# Comm.net
KiCad netlist of a schematic drawn in Altium Designer
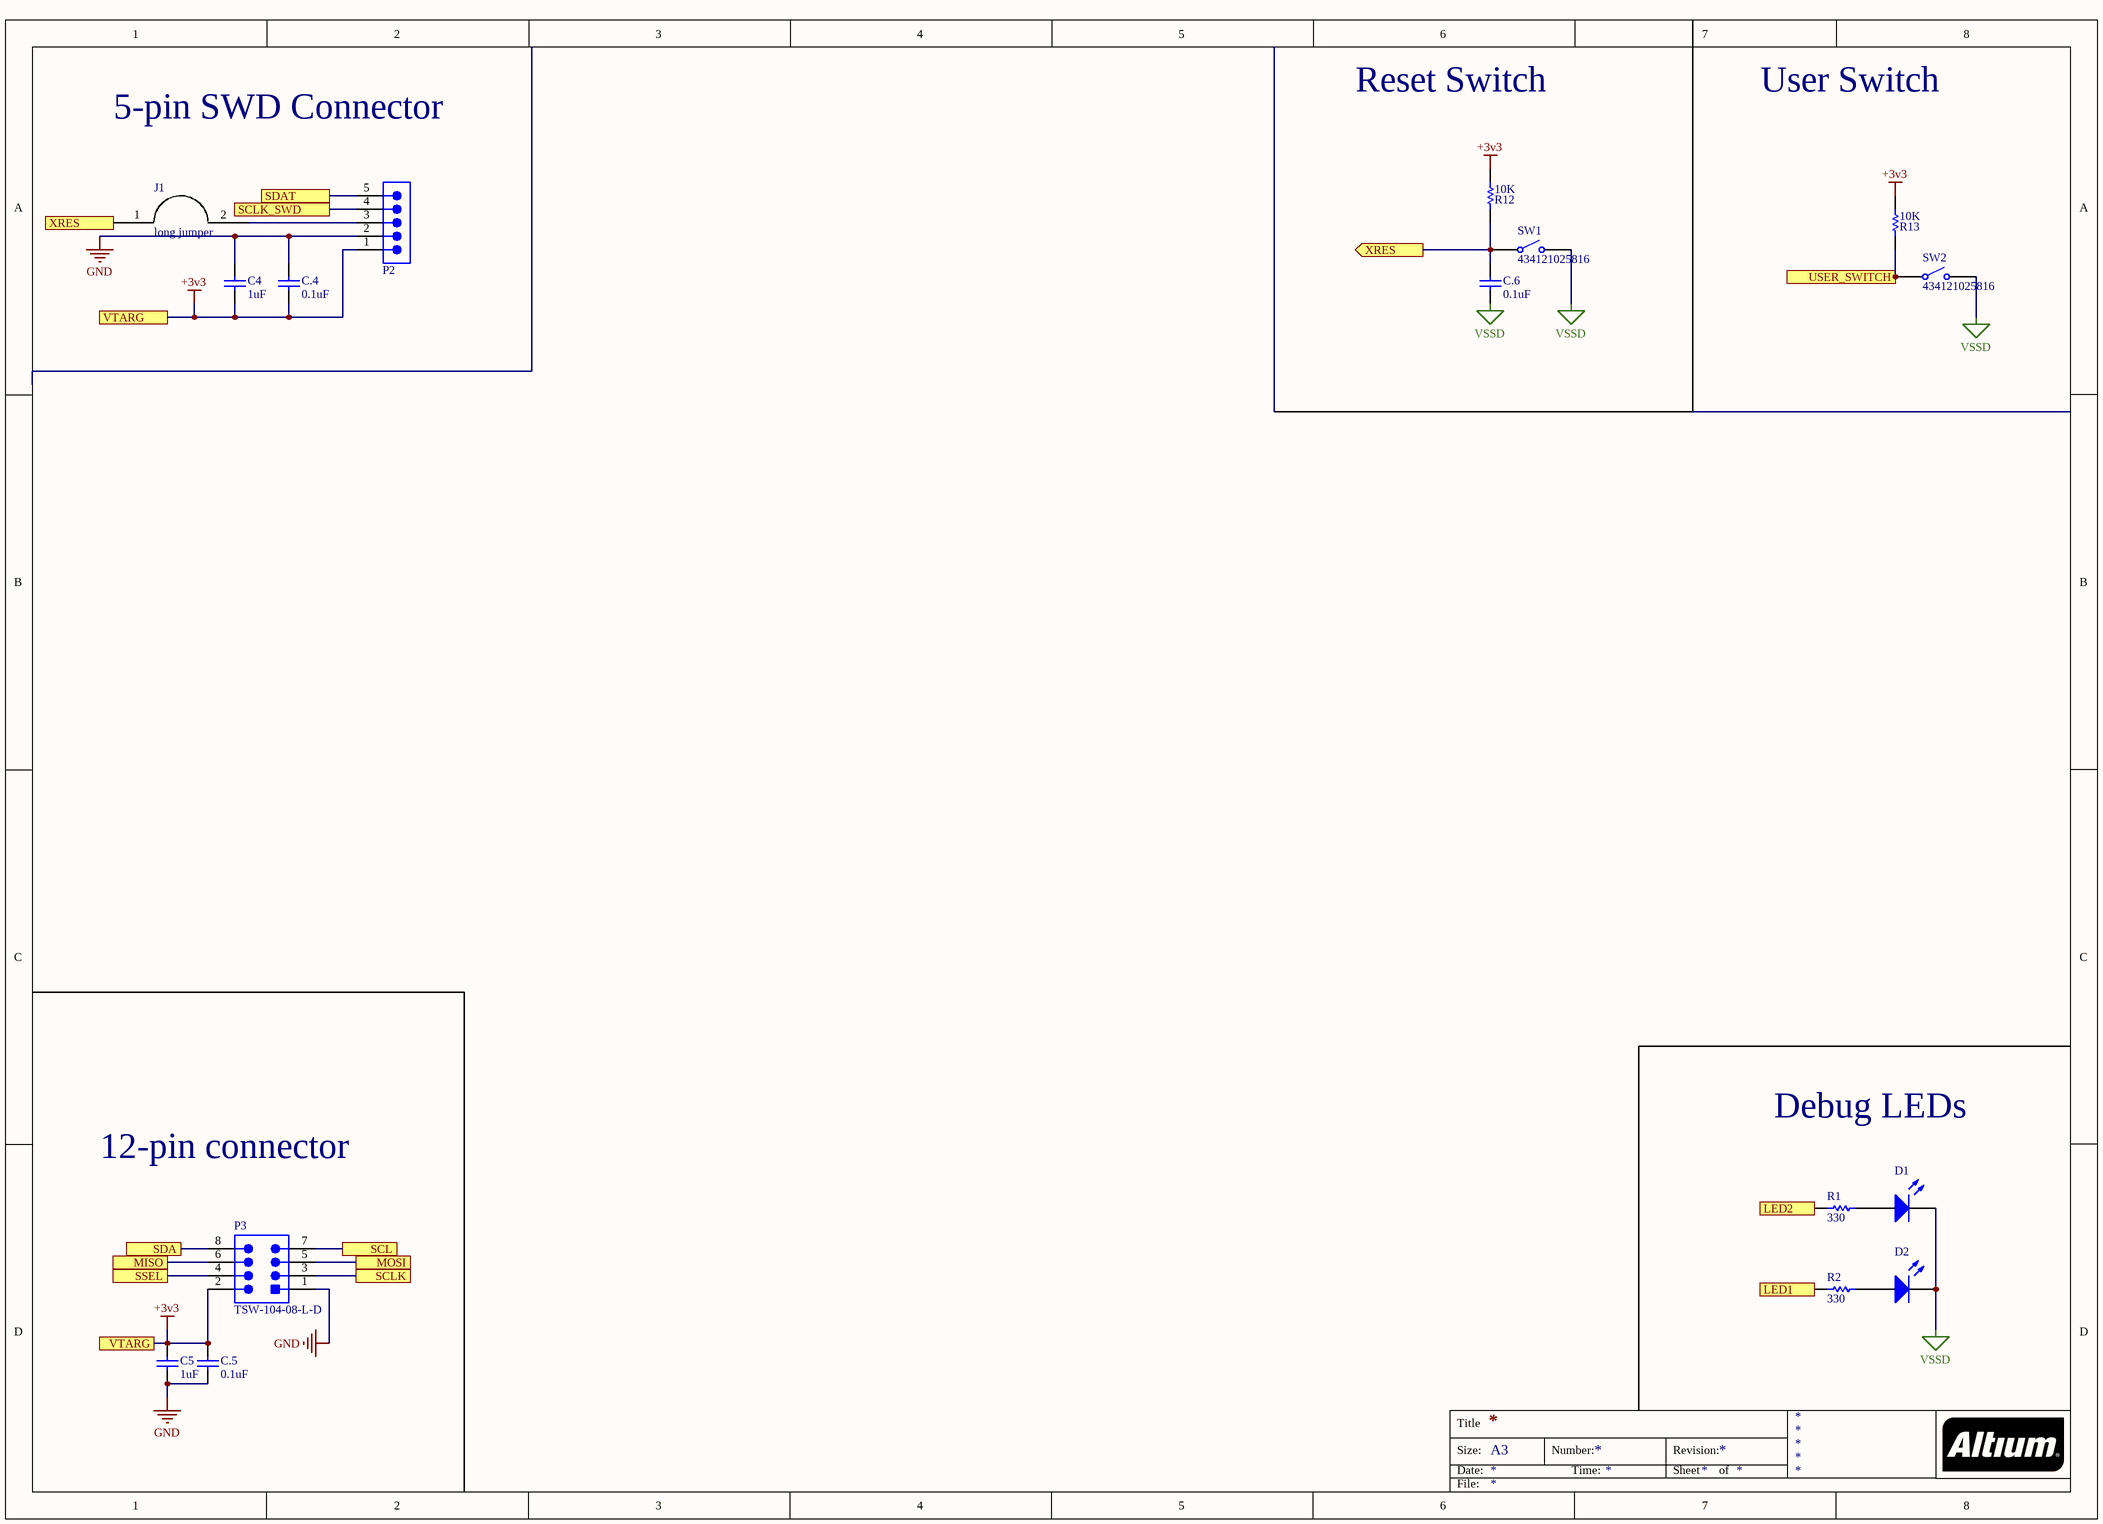
[diagram p0: Comm.SchDoc]

(export (version "E")
  (design (tool "Eeschema 10.0.6"))
  (components
    (comp (ref "C.4")
      (value "0.1uF")
      (footprint "CAPC0603(1608)100_N")
      (description "CAP 0.1 uF 50V ±20% 0603 (1608 Metric) Thickness 1mm SMD")
      (fields (field (name "TOLERANCE") "Â±20%"))
      (libsource (lib "Altium Content Vault") (part "CAP"))
    )
    (comp (ref "C.5")
      (value "0.1uF")
      (footprint "CAPC0603(1608)100_N")
      (description "CAP 0.1 uF 50V ±20% 0603 (1608 Metric) Thickness 1mm SMD")
      (fields (field (name "TOLERANCE") "Â±20%"))
      (libsource (lib "Altium Content Vault") (part "CAP"))
    )
    (comp (ref "C.6")
      (value "0.1uF")
      (footprint "CAPC0603(1608)100_N")
      (description "CAP 0.1 uF 50V ±20% 0603 (1608 Metric) Thickness 1mm SMD")
      (fields (field (name "TOLERANCE") "Â±20%"))
      (libsource (lib "Altium Content Vault") (part "CAP"))
    )
    (comp (ref "C4")
      (value "1uF")
      (footprint "CAPC0603(1608)100_N")
      (description "CAP 1uF 50V ±20% 0603 (1608 Metric) Thickness 1mm SMD")
      (fields (field (name "TOLERANCE") "Â±20%"))
      (libsource (lib "Altium Content Vault") (part "CAP"))
    )
    (comp (ref "C5")
      (value "1uF")
      (footprint "CAPC0603(1608)100_N")
      (description "CAP 1uF 50V ±20% 0603 (1608 Metric) Thickness 1mm SMD")
      (fields (field (name "TOLERANCE") "Â±20%"))
      (libsource (lib "Altium Content Vault") (part "CAP"))
    )
    (comp (ref "D1")
      (value "150060BS75000")
      (footprint "0603_A")
      (description "SMD mono-color Chip LED, WL-SMCW, Blue")
      (fields (field (name "MANUFACTURER") "Wuerth Elektronik"))
      (libsource (lib "Altium Content Vault") (part "WE-LED_K1A2-2"))
    )
    (comp (ref "D2")
      (value "150060BS75000")
      (footprint "0603_A")
      (description "SMD mono-color Chip LED, WL-SMCW, Blue")
      (fields (field (name "MANUFACTURER") "Wuerth Elektronik"))
      (libsource (lib "Altium Content Vault") (part "WE-LED_K1A2-2"))
    )
    (comp (ref "J1")
      (value "long jumper")
      (footprint "PCBComponent_1")
      (libsource (lib "net_ties") (part "long jumper"))
    )
    (comp (ref "P2")
      (value "MTLW-105-05-L-S-190")
      (footprint "SMTC-MTLW-105-05-X-S-190")
      (fields (field (name "MANUFACTURER") "Samtec"))
      (libsource (lib "Altium Content Vault") (part "SMTC-MTLW-105-05-X-S-190"))
    )
    (comp (ref "P3")
      (value "TSW-104-08-L-D")
      (footprint "SMTC-TSW-104-08-L-D_V")
      (fields (field (name "MANUFACTURER") "Samtec"))
      (libsource (lib "Altium Content Vault") (part "CN-2P-M-R8"))
    )
    (comp (ref "R1")
      (value "330")
      (footprint "RESC0603(1608)_L")
      (description "330R 0.1W 5% 0603 (1608 Metric)  SMD")
      (fields (field (name "TOLERANCE") "5 %") (field (name "POWER") "0.1 W"))
      (libsource (lib "Altium Content Vault") (part "RES"))
    )
    (comp (ref "R2")
      (value "330")
      (footprint "RESC0603(1608)_L")
      (description "330R 0.1W 5% 0603 (1608 Metric)  SMD")
      (fields (field (name "TOLERANCE") "5 %") (field (name "POWER") "0.1 W"))
      (libsource (lib "Altium Content Vault") (part "RES"))
    )
    (comp (ref "R12")
      (value "10K")
      (footprint "RESC1608X55X25ML10T15")
      (description "Chip Resistor, 4.7 KOhm, +/- 5%, 100 mW, -55 to 155 degC, 0603 (1608 Metric), RoHS, Tape and Reel")
      (fields (field (name "TOLERANCE") "5%") (field (name "MANUFACTURER") "Yageo"))
      (libsource (lib "Altium Content Vault") (part "RES-2"))
    )
    (comp (ref "R13")
      (value "10K")
      (footprint "RESC1608X55X25ML10T15")
      (description "Chip Resistor, 4.7 KOhm, +/- 5%, 100 mW, -55 to 155 degC, 0603 (1608 Metric), RoHS, Tape and Reel")
      (fields (field (name "TOLERANCE") "5%") (field (name "MANUFACTURER") "Yageo"))
      (libsource (lib "Altium Content Vault") (part "RES-2"))
    )
    (comp (ref "SW1")
      (value "434121025816")
      (footprint "434121025816")
      (description "WS-TASV SMD Tact Switch 6.0X3.8 mm")
      (fields (field (name "MANUFACTURER") "Wuerth Elektronik"))
      (libsource (lib "Altium Content Vault") (part "WE-TACT-SW-2"))
    )
    (comp (ref "SW2")
      (value "434121025816")
      (footprint "434121025816")
      (description "WS-TASV SMD Tact Switch 6.0X3.8 mm")
      (fields (field (name "MANUFACTURER") "Wuerth Elektronik"))
      (libsource (lib "Altium Content Vault") (part "WE-TACT-SW-2"))
    )
  )
  (nets
    (net (code "1") (name "+3v3") (class "Default")
      (node (ref "C.4") (pin "1") (pinfunction "1_1") (pintype "passive"))
      (node (ref "C.5") (pin "2") (pinfunction "2_2") (pintype "passive"))
      (node (ref "C4") (pin "1") (pinfunction "1_1") (pintype "passive"))
      (node (ref "C5") (pin "2") (pinfunction "2_2") (pintype "passive"))
      (node (ref "P2") (pin "1") (pinfunction "1_1") (pintype "passive"))
      (node (ref "P3") (pin "2") (pinfunction "2_2") (pintype "passive"))
      (node (ref "R12") (pin "2") (pinfunction "2_2") (pintype "passive"))
      (node (ref "R13") (pin "2") (pinfunction "2_2") (pintype "passive"))
    )
    (net (code "2") (name "/LED1") (class "Default")
      (node (ref "R2") (pin "1") (pinfunction "1_1") (pintype "passive"))
    )
    (net (code "3") (name "/LED2") (class "Default")
      (node (ref "R1") (pin "1") (pinfunction "1_1") (pintype "passive"))
    )
    (net (code "4") (name "/MISO") (class "Default")
      (node (ref "P3") (pin "6") (pinfunction "6_6") (pintype "passive"))
    )
    (net (code "5") (name "/MOSI") (class "Default")
      (node (ref "P3") (pin "5") (pinfunction "5_5") (pintype "passive"))
    )
    (net (code "6") (name "/SCL") (class "Default")
      (node (ref "P3") (pin "7") (pinfunction "7_7") (pintype "passive"))
    )
    (net (code "7") (name "/SCLK") (class "Default")
      (node (ref "P3") (pin "3") (pinfunction "3_3") (pintype "passive"))
    )
    (net (code "8") (name "/SCLK_SWD") (class "Default")
      (node (ref "P2") (pin "4") (pinfunction "4_4") (pintype "passive"))
    )
    (net (code "9") (name "/SDA") (class "Default")
      (node (ref "P3") (pin "8") (pinfunction "8_8") (pintype "passive"))
    )
    (net (code "10") (name "/SDAT") (class "Default")
      (node (ref "P2") (pin "5") (pinfunction "5_5") (pintype "passive"))
    )
    (net (code "11") (name "/SSEL") (class "Default")
      (node (ref "P3") (pin "4") (pinfunction "4_4") (pintype "passive"))
    )
    (net (code "12") (name "/USER_SWITCH") (class "Default")
      (node (ref "R13") (pin "1") (pinfunction "1_1") (pintype "passive"))
      (node (ref "SW2") (pin "1") (pinfunction "1_1") (pintype "passive"))
    )
    (net (code "13") (name "/XRES") (class "Default")
      (node (ref "C.6") (pin "2") (pinfunction "2_2") (pintype "passive"))
      (node (ref "J1") (pin "1") (pinfunction "1_1") (pintype "passive"))
      (node (ref "R12") (pin "1") (pinfunction "1_1") (pintype "passive"))
      (node (ref "SW1") (pin "1") (pinfunction "1_1") (pintype "passive"))
    )
    (net (code "14") (name "GND") (class "Default")
      (node (ref "C.4") (pin "2") (pinfunction "2_2") (pintype "passive"))
      (node (ref "C.5") (pin "1") (pinfunction "1_1") (pintype "passive"))
      (node (ref "C4") (pin "2") (pinfunction "2_2") (pintype "passive"))
      (node (ref "C5") (pin "1") (pinfunction "1_1") (pintype "passive"))
      (node (ref "P2") (pin "2") (pinfunction "2_2") (pintype "passive"))
      (node (ref "P3") (pin "1") (pinfunction "1_1") (pintype "passive"))
    )
    (net (code "15") (name "Net-(D1-A)") (class "Default")
      (node (ref "D1") (pin "2") (pinfunction "A_2") (pintype "passive"))
      (node (ref "R1") (pin "2") (pinfunction "2_2") (pintype "passive"))
    )
    (net (code "16") (name "Net-(D2-A)") (class "Default")
      (node (ref "D2") (pin "2") (pinfunction "A_2") (pintype "passive"))
      (node (ref "R2") (pin "2") (pinfunction "2_2") (pintype "passive"))
    )
    (net (code "17") (name "Net-(J1-Pad2)") (class "Default")
      (node (ref "J1") (pin "2") (pinfunction "2_2") (pintype "passive"))
      (node (ref "P2") (pin "3") (pinfunction "3_3") (pintype "passive"))
    )
    (net (code "18") (name "VSSD") (class "Default")
      (node (ref "C.6") (pin "1") (pinfunction "1_1") (pintype "passive"))
      (node (ref "D1") (pin "1") (pinfunction "K_1") (pintype "passive"))
      (node (ref "D2") (pin "1") (pinfunction "K_1") (pintype "passive"))
      (node (ref "SW1") (pin "2") (pinfunction "2_2") (pintype "passive"))
      (node (ref "SW2") (pin "2") (pinfunction "2_2") (pintype "passive"))
    )
  )
)
